# LEDSEQUEUECER.net
KiCad netlist of a schematic drawn in Altium Designer
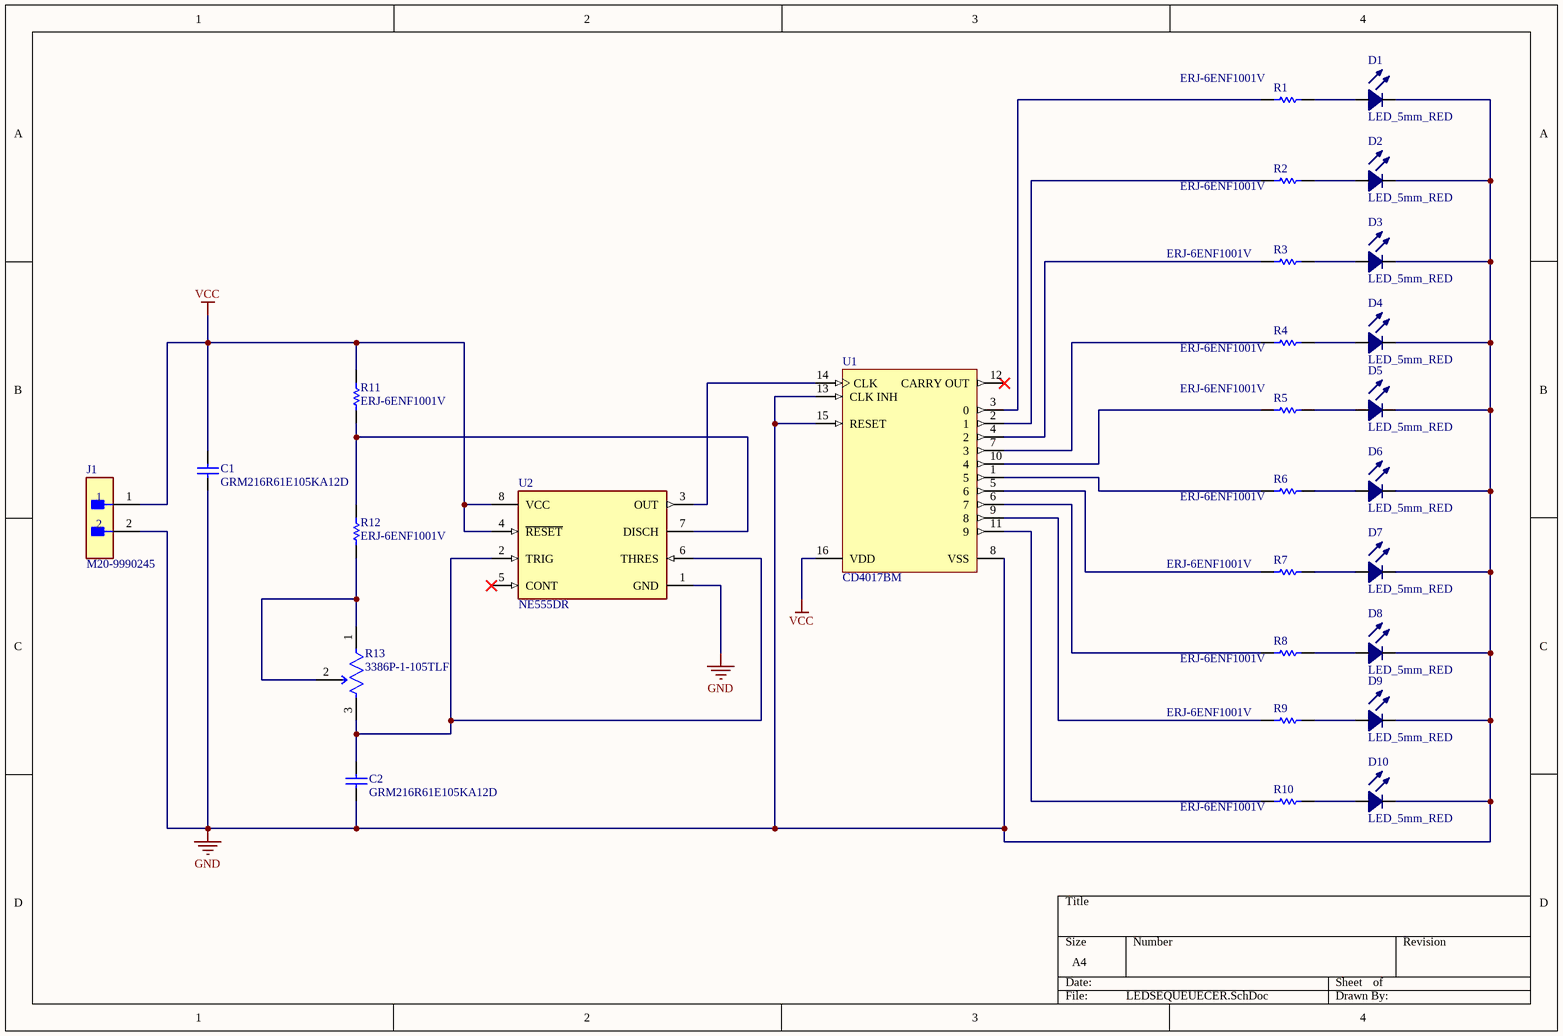
[diagram p0: LEDSEQUEUECER.SchDoc]

(export (version "E")
  (design (tool "Eeschema 10.0.6"))
  (components
    (comp (ref "C1")
      (value "GRM216R61E105KA12D")
      (footprint "CAPC2013X70X45NL10T25")
      (fields (field (name "MANUFACTURER") "Murata"))
      (libsource (lib "Altium Content Vault") (part "CAP"))
    )
    (comp (ref "C2")
      (value "GRM216R61E105KA12D")
      (footprint "CAPC2013X70X45NL10T25")
      (fields (field (name "MANUFACTURER") "Murata"))
      (libsource (lib "Altium Content Vault") (part "CAP"))
    )
    (comp (ref "D1")
      (value "LED_5mm_RED")
      (footprint "LED_5mm_RED")
      (description "LED PTH 5mm Red.")
      (libsource (lib "LED") (part "LED_5mm_RED"))
    )
    (comp (ref "D2")
      (value "LED_5mm_RED")
      (footprint "LED_5mm_RED")
      (description "LED PTH 5mm Red.")
      (libsource (lib "LED") (part "LED_5mm_RED"))
    )
    (comp (ref "D3")
      (value "LED_5mm_RED")
      (footprint "LED_5mm_RED")
      (description "LED PTH 5mm Red.")
      (libsource (lib "LED") (part "LED_5mm_RED"))
    )
    (comp (ref "D4")
      (value "LED_5mm_RED")
      (footprint "LED_5mm_RED")
      (description "LED PTH 5mm Red.")
      (libsource (lib "LED") (part "LED_5mm_RED"))
    )
    (comp (ref "D5")
      (value "LED_5mm_RED")
      (footprint "LED_5mm_RED")
      (description "LED PTH 5mm Red.")
      (libsource (lib "LED") (part "LED_5mm_RED"))
    )
    (comp (ref "D6")
      (value "LED_5mm_RED")
      (footprint "LED_5mm_RED")
      (description "LED PTH 5mm Red.")
      (libsource (lib "LED") (part "LED_5mm_RED"))
    )
    (comp (ref "D7")
      (value "LED_5mm_RED")
      (footprint "LED_5mm_RED")
      (description "LED PTH 5mm Red.")
      (libsource (lib "LED") (part "LED_5mm_RED"))
    )
    (comp (ref "D8")
      (value "LED_5mm_RED")
      (footprint "LED_5mm_RED")
      (description "LED PTH 5mm Red.")
      (libsource (lib "LED") (part "LED_5mm_RED"))
    )
    (comp (ref "D9")
      (value "LED_5mm_RED")
      (footprint "LED_5mm_RED")
      (description "LED PTH 5mm Red.")
      (libsource (lib "LED") (part "LED_5mm_RED"))
    )
    (comp (ref "D10")
      (value "LED_5mm_RED")
      (footprint "LED_5mm_RED")
      (description "LED PTH 5mm Red.")
      (libsource (lib "LED") (part "LED_5mm_RED"))
    )
    (comp (ref "J1")
      (value "M20-9990245")
      (footprint "FP-M20-9990245-MFG")
      (description "CONN HEADER VERT 2POS 2.54MM")
      (fields (field (name "VOLTAGE") "50V"))
      (libsource (lib "Altium Content Vault") (part "3bc925449376181038e59eaffc5286c"))
    )
    (comp (ref "R1")
      (value "ERJ-6ENF1001V")
      (footprint "RESC2013X70X40LL20T20")
      (description "Chip Resistor, 1 KOhm, +/- 1%, 0.125 W, -55 to 155 degC, 0805 (2012 Metric), RoHS, Tape and Reel")
      (fields (field (name "MANUFACTURER") "Panasonic"))
      (libsource (lib "Altium Content Vault") (part "RES-2"))
    )
    (comp (ref "R2")
      (value "ERJ-6ENF1001V")
      (footprint "RESC2013X70X40LL20T20")
      (description "Chip Resistor, 1 KOhm, +/- 1%, 0.125 W, -55 to 155 degC, 0805 (2012 Metric), RoHS, Tape and Reel")
      (fields (field (name "MANUFACTURER") "Panasonic"))
      (libsource (lib "Altium Content Vault") (part "RES-2"))
    )
    (comp (ref "R3")
      (value "ERJ-6ENF1001V")
      (footprint "RESC2013X70X40LL20T20")
      (description "Chip Resistor, 1 KOhm, +/- 1%, 0.125 W, -55 to 155 degC, 0805 (2012 Metric), RoHS, Tape and Reel")
      (fields (field (name "MANUFACTURER") "Panasonic"))
      (libsource (lib "Altium Content Vault") (part "RES-2"))
    )
    (comp (ref "R4")
      (value "ERJ-6ENF1001V")
      (footprint "RESC2013X70X40LL20T20")
      (description "Chip Resistor, 1 KOhm, +/- 1%, 0.125 W, -55 to 155 degC, 0805 (2012 Metric), RoHS, Tape and Reel")
      (fields (field (name "MANUFACTURER") "Panasonic"))
      (libsource (lib "Altium Content Vault") (part "RES-2"))
    )
    (comp (ref "R5")
      (value "ERJ-6ENF1001V")
      (footprint "RESC2013X70X40LL20T20")
      (description "Chip Resistor, 1 KOhm, +/- 1%, 0.125 W, -55 to 155 degC, 0805 (2012 Metric), RoHS, Tape and Reel")
      (fields (field (name "MANUFACTURER") "Panasonic"))
      (libsource (lib "Altium Content Vault") (part "RES-2"))
    )
    (comp (ref "R6")
      (value "ERJ-6ENF1001V")
      (footprint "RESC2013X70X40LL20T20")
      (description "Chip Resistor, 1 KOhm, +/- 1%, 0.125 W, -55 to 155 degC, 0805 (2012 Metric), RoHS, Tape and Reel")
      (fields (field (name "MANUFACTURER") "Panasonic"))
      (libsource (lib "Altium Content Vault") (part "RES-2"))
    )
    (comp (ref "R7")
      (value "ERJ-6ENF1001V")
      (footprint "RESC2013X70X40LL20T20")
      (description "Chip Resistor, 1 KOhm, +/- 1%, 0.125 W, -55 to 155 degC, 0805 (2012 Metric), RoHS, Tape and Reel")
      (fields (field (name "MANUFACTURER") "Panasonic"))
      (libsource (lib "Altium Content Vault") (part "RES-2"))
    )
    (comp (ref "R8")
      (value "ERJ-6ENF1001V")
      (footprint "RESC2013X70X40LL20T20")
      (description "Chip Resistor, 1 KOhm, +/- 1%, 0.125 W, -55 to 155 degC, 0805 (2012 Metric), RoHS, Tape and Reel")
      (fields (field (name "MANUFACTURER") "Panasonic"))
      (libsource (lib "Altium Content Vault") (part "RES-2"))
    )
    (comp (ref "R9")
      (value "ERJ-6ENF1001V")
      (footprint "RESC2013X70X40LL20T20")
      (description "Chip Resistor, 1 KOhm, +/- 1%, 0.125 W, -55 to 155 degC, 0805 (2012 Metric), RoHS, Tape and Reel")
      (fields (field (name "MANUFACTURER") "Panasonic"))
      (libsource (lib "Altium Content Vault") (part "RES-2"))
    )
    (comp (ref "R10")
      (value "ERJ-6ENF1001V")
      (footprint "RESC2013X70X40LL20T20")
      (description "Chip Resistor, 1 KOhm, +/- 1%, 0.125 W, -55 to 155 degC, 0805 (2012 Metric), RoHS, Tape and Reel")
      (fields (field (name "MANUFACTURER") "Panasonic"))
      (libsource (lib "Altium Content Vault") (part "RES-2"))
    )
    (comp (ref "R11")
      (value "ERJ-6ENF1001V")
      (footprint "RESC2013X70X40LL20T20")
      (description "Chip Resistor, 1 KOhm, +/- 1%, 0.125 W, -55 to 155 degC, 0805 (2012 Metric), RoHS, Tape and Reel")
      (fields (field (name "MANUFACTURER") "Panasonic"))
      (libsource (lib "Altium Content Vault") (part "RES-2"))
    )
    (comp (ref "R12")
      (value "ERJ-6ENF1001V")
      (footprint "RESC2013X70X40LL20T20")
      (description "Chip Resistor, 1 KOhm, +/- 1%, 0.125 W, -55 to 155 degC, 0805 (2012 Metric), RoHS, Tape and Reel")
      (fields (field (name "MANUFACTURER") "Panasonic"))
      (libsource (lib "Altium Content Vault") (part "RES-2"))
    )
    (comp (ref "R13")
      (value "3386P-1-105TLF")
      (footprint "FP-3386P-MFG")
      (description "TRIMMER 1M OHM 0.5W PC PIN TOP")
      (fields (field (name "TOLERANCE") "10%") (field (name "MANUFACTURER") "Bourns Inc."))
      (libsource (lib "Altium Content Vault") (part "2dcfd2547301a7d3209a5e99acfd772"))
    )
    (comp (ref "U1")
      (value "CD4017BM")
      (footprint "D0016A_N")
      (description "CMOS Decade Counter with 10 Decoded Outputs, D0016A, TUBE")
      (fields
        (field (name "GENERIC PART NUMBER") "CD4017B")
        (field (name "MANUFACTURER") "Texas Instruments")
      )
      (libsource (lib "Altium Content Vault") (part "TI-CD4017B-16"))
    )
    (comp (ref "U2")
      (value "NE555DR")
      (footprint "FP-D0008A-IPC_A")
      (description "IC OSC SGL TIMER 100KHZ 8-SOIC")
      (libsource (lib "Altium Content Vault") (part "a29bba90211dec1890110b94dad7d53"))
    )
  )
  (nets
    (net (code "1") (name "GND") (class "Default")
      (node (ref "C1") (pin "1") (pinfunction "1_1") (pintype "passive"))
      (node (ref "C2") (pin "1") (pinfunction "1_1") (pintype "passive"))
      (node (ref "D1") (pin "2") (pinfunction "2_2") (pintype "passive"))
      (node (ref "D10") (pin "2") (pinfunction "2_2") (pintype "passive"))
      (node (ref "D2") (pin "2") (pinfunction "2_2") (pintype "passive"))
      (node (ref "D3") (pin "2") (pinfunction "2_2") (pintype "passive"))
      (node (ref "D4") (pin "2") (pinfunction "2_2") (pintype "passive"))
      (node (ref "D5") (pin "2") (pinfunction "2_2") (pintype "passive"))
      (node (ref "D6") (pin "2") (pinfunction "2_2") (pintype "passive"))
      (node (ref "D7") (pin "2") (pinfunction "2_2") (pintype "passive"))
      (node (ref "D8") (pin "2") (pinfunction "2_2") (pintype "passive"))
      (node (ref "D9") (pin "2") (pinfunction "2_2") (pintype "passive"))
      (node (ref "J1") (pin "2") (pinfunction "2_2") (pintype "passive"))
      (node (ref "U1") (pin "13") (pinfunction "CLK_INH_13") (pintype "input"))
      (node (ref "U1") (pin "15") (pinfunction "RESET_15") (pintype "input"))
      (node (ref "U1") (pin "8") (pinfunction "VSS_8") (pintype "power_in"))
      (node (ref "U2") (pin "1") (pinfunction "GND_1") (pintype "power_in"))
    )
    (net (code "2") (name "Net-(D1-Pad1)") (class "Default")
      (node (ref "D1") (pin "1") (pinfunction "1_1") (pintype "passive"))
      (node (ref "R1") (pin "2") (pinfunction "2_2") (pintype "passive"))
    )
    (net (code "3") (name "Net-(D2-Pad1)") (class "Default")
      (node (ref "D2") (pin "1") (pinfunction "1_1") (pintype "passive"))
      (node (ref "R2") (pin "2") (pinfunction "2_2") (pintype "passive"))
    )
    (net (code "4") (name "Net-(D3-Pad1)") (class "Default")
      (node (ref "D3") (pin "1") (pinfunction "1_1") (pintype "passive"))
      (node (ref "R3") (pin "2") (pinfunction "2_2") (pintype "passive"))
    )
    (net (code "5") (name "Net-(D4-Pad1)") (class "Default")
      (node (ref "D4") (pin "1") (pinfunction "1_1") (pintype "passive"))
      (node (ref "R4") (pin "2") (pinfunction "2_2") (pintype "passive"))
    )
    (net (code "6") (name "Net-(D5-Pad1)") (class "Default")
      (node (ref "D5") (pin "1") (pinfunction "1_1") (pintype "passive"))
      (node (ref "R5") (pin "2") (pinfunction "2_2") (pintype "passive"))
    )
    (net (code "7") (name "Net-(D6-Pad1)") (class "Default")
      (node (ref "D6") (pin "1") (pinfunction "1_1") (pintype "passive"))
      (node (ref "R6") (pin "2") (pinfunction "2_2") (pintype "passive"))
    )
    (net (code "8") (name "Net-(D7-Pad1)") (class "Default")
      (node (ref "D7") (pin "1") (pinfunction "1_1") (pintype "passive"))
      (node (ref "R7") (pin "2") (pinfunction "2_2") (pintype "passive"))
    )
    (net (code "9") (name "Net-(D8-Pad1)") (class "Default")
      (node (ref "D8") (pin "1") (pinfunction "1_1") (pintype "passive"))
      (node (ref "R8") (pin "2") (pinfunction "2_2") (pintype "passive"))
    )
    (net (code "10") (name "Net-(D9-Pad1)") (class "Default")
      (node (ref "D9") (pin "1") (pinfunction "1_1") (pintype "passive"))
      (node (ref "R9") (pin "2") (pinfunction "2_2") (pintype "passive"))
    )
    (net (code "11") (name "Net-(D10-Pad1)") (class "Default")
      (node (ref "D10") (pin "1") (pinfunction "1_1") (pintype "passive"))
      (node (ref "R10") (pin "2") (pinfunction "2_2") (pintype "passive"))
    )
    (net (code "12") (name "Net-(R13-CCW)") (class "Default")
      (node (ref "R12") (pin "1") (pinfunction "1_1") (pintype "passive"))
      (node (ref "R13") (pin "1") (pinfunction "CCW_1") (pintype "passive"))
      (node (ref "R13") (pin "2") (pinfunction "WIPER_2") (pintype "passive"))
    )
    (net (code "13") (name "Net-(R13-CW)") (class "Default")
      (node (ref "C2") (pin "2") (pinfunction "2_2") (pintype "passive"))
      (node (ref "R13") (pin "3") (pinfunction "CW_3") (pintype "passive"))
      (node (ref "U2") (pin "2") (pinfunction "TRIG_2") (pintype "input"))
      (node (ref "U2") (pin "6") (pinfunction "THRES_6") (pintype "input"))
    )
    (net (code "14") (name "Net-(U1-0)") (class "Default")
      (node (ref "R1") (pin "1") (pinfunction "1_1") (pintype "passive"))
      (node (ref "U1") (pin "3") (pinfunction "0_3") (pintype "output"))
    )
    (net (code "15") (name "Net-(U1-1)") (class "Default")
      (node (ref "R2") (pin "1") (pinfunction "1_1") (pintype "passive"))
      (node (ref "U1") (pin "2") (pinfunction "1_2") (pintype "output"))
    )
    (net (code "16") (name "Net-(U1-2)") (class "Default")
      (node (ref "R3") (pin "1") (pinfunction "1_1") (pintype "passive"))
      (node (ref "U1") (pin "4") (pinfunction "2_4") (pintype "output"))
    )
    (net (code "17") (name "Net-(U1-3)") (class "Default")
      (node (ref "R4") (pin "1") (pinfunction "1_1") (pintype "passive"))
      (node (ref "U1") (pin "7") (pinfunction "3_7") (pintype "output"))
    )
    (net (code "18") (name "Net-(U1-4)") (class "Default")
      (node (ref "R5") (pin "1") (pinfunction "1_1") (pintype "passive"))
      (node (ref "U1") (pin "10") (pinfunction "4_10") (pintype "output"))
    )
    (net (code "19") (name "Net-(U1-5)") (class "Default")
      (node (ref "R6") (pin "1") (pinfunction "1_1") (pintype "passive"))
      (node (ref "U1") (pin "1") (pinfunction "5_1") (pintype "output"))
    )
    (net (code "20") (name "Net-(U1-6)") (class "Default")
      (node (ref "R7") (pin "1") (pinfunction "1_1") (pintype "passive"))
      (node (ref "U1") (pin "5") (pinfunction "6_5") (pintype "output"))
    )
    (net (code "21") (name "Net-(U1-7)") (class "Default")
      (node (ref "R8") (pin "1") (pinfunction "1_1") (pintype "passive"))
      (node (ref "U1") (pin "6") (pinfunction "7_6") (pintype "output"))
    )
    (net (code "22") (name "Net-(U1-8)") (class "Default")
      (node (ref "R9") (pin "1") (pinfunction "1_1") (pintype "passive"))
      (node (ref "U1") (pin "9") (pinfunction "8_9") (pintype "output"))
    )
    (net (code "23") (name "Net-(U1-9)") (class "Default")
      (node (ref "R10") (pin "1") (pinfunction "1_1") (pintype "passive"))
      (node (ref "U1") (pin "11") (pinfunction "9_11") (pintype "output"))
    )
    (net (code "24") (name "Net-(U1-CLK)") (class "Default")
      (node (ref "U1") (pin "14") (pinfunction "CLK_14") (pintype "input"))
      (node (ref "U2") (pin "3") (pinfunction "OUT_3") (pintype "output"))
    )
    (net (code "25") (name "Net-(U2-DISCH)") (class "Default")
      (node (ref "R11") (pin "1") (pinfunction "1_1") (pintype "passive"))
      (node (ref "R12") (pin "2") (pinfunction "2_2") (pintype "passive"))
      (node (ref "U2") (pin "7") (pinfunction "DISCH_7") (pintype "open_collector"))
    )
    (net (code "26") (name "VCC") (class "Default")
      (node (ref "C1") (pin "2") (pinfunction "2_2") (pintype "passive"))
      (node (ref "J1") (pin "1") (pinfunction "1_1") (pintype "passive"))
      (node (ref "R11") (pin "2") (pinfunction "2_2") (pintype "passive"))
      (node (ref "U1") (pin "16") (pinfunction "VDD_16") (pintype "power_in"))
      (node (ref "U2") (pin "4") (pinfunction "~{RESET}_4") (pintype "input"))
      (node (ref "U2") (pin "8") (pinfunction "VCC_8") (pintype "power_in"))
    )
    (net (code "27") (name "unconnected-(U1-CARRY_OUT-Pad12)") (class "Default")
      (node (ref "U1") (pin "12") (pinfunction "CARRY_OUT_12") (pintype "output+no_connect"))
    )
    (net (code "28") (name "unconnected-(U2-CONT-Pad5)") (class "Default")
      (node (ref "U2") (pin "5") (pinfunction "CONT_5") (pintype "input+no_connect"))
    )
  )
)
